# fpga_power.net
KiCad netlist of a schematic drawn in Altium Designer
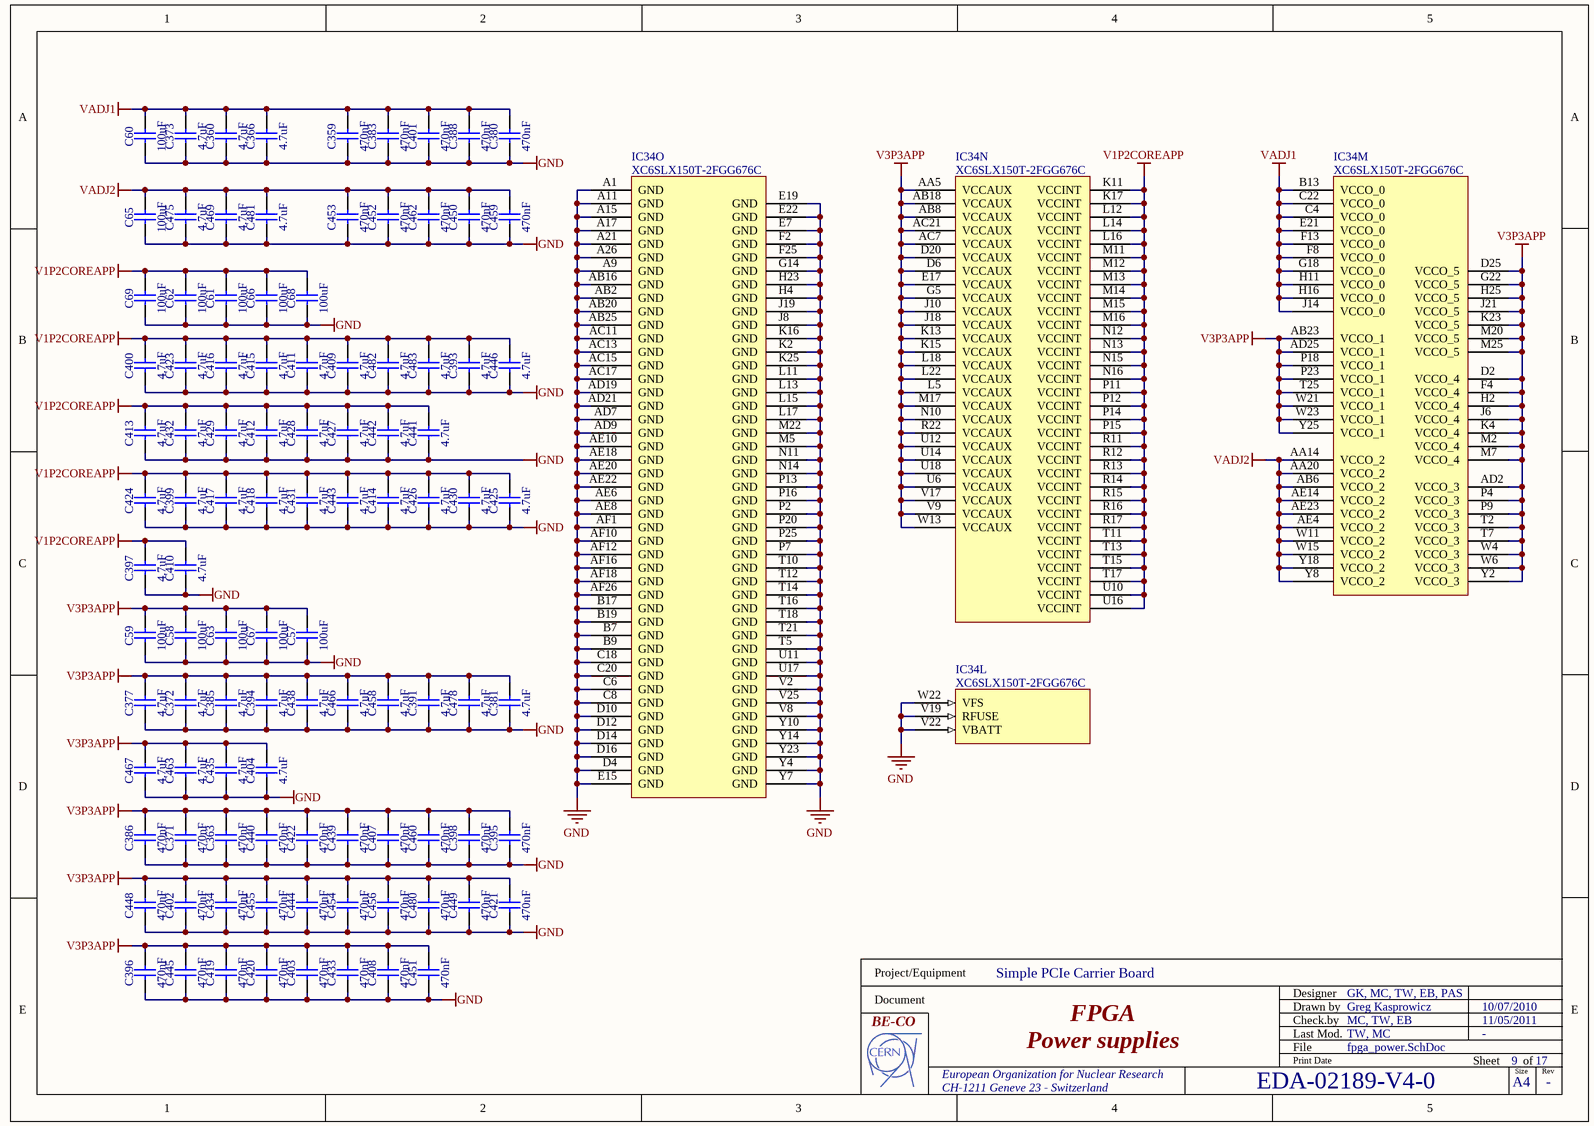
[diagram p0: fpga_power.SchDoc]

(export (version "E")
  (design (tool "Eeschema 10.0.6"))
  (components
    (comp (ref "C57")
      (value "100uF")
      (footprint "CAPC3225X270N")
      (description "Non-polarised capacitor")
      (fields
        (field (name "PART NUMBER") "CC1210_100UF_6.3V_20%_X5R")
        (field (name "VOLTAGE") "6.3V")
        (field (name "AUTHOR") "CERN DEM JLC")
      )
      (libsource (lib "Capacitors") (part "Capacitor - non polarized"))
    )
    (comp (ref "C58")
      (value "100uF")
      (footprint "CAPC3225X270N")
      (description "Non-polarised capacitor")
      (fields
        (field (name "PART NUMBER") "CC1210_100UF_6.3V_20%_X5R")
        (field (name "VOLTAGE") "6.3V")
        (field (name "AUTHOR") "CERN DEM JLC")
      )
      (libsource (lib "Capacitors") (part "Capacitor - non polarized"))
    )
    (comp (ref "C59")
      (value "100uF")
      (footprint "CAPC3225X270N")
      (description "Non-polarised capacitor")
      (fields
        (field (name "PART NUMBER") "CC1210_100UF_6.3V_20%_X5R")
        (field (name "VOLTAGE") "6.3V")
        (field (name "AUTHOR") "CERN DEM JLC")
      )
      (libsource (lib "Capacitors") (part "Capacitor - non polarized"))
    )
    (comp (ref "C60")
      (value "100uF")
      (footprint "CAPC3225X270N")
      (description "Non-polarised capacitor")
      (fields
        (field (name "PART NUMBER") "CC1210_100UF_6.3V_20%_X5R")
        (field (name "VOLTAGE") "6.3V")
        (field (name "AUTHOR") "CERN DEM JLC")
      )
      (libsource (lib "Capacitors") (part "Capacitor - non polarized"))
    )
    (comp (ref "C61")
      (value "100uF")
      (footprint "CAPC3225X270N")
      (description "Non-polarised capacitor")
      (fields
        (field (name "PART NUMBER") "CC1210_100UF_6.3V_20%_X5R")
        (field (name "VOLTAGE") "6.3V")
        (field (name "AUTHOR") "CERN DEM JLC")
      )
      (libsource (lib "Capacitors") (part "Capacitor - non polarized"))
    )
    (comp (ref "C62")
      (value "100uF")
      (footprint "CAPC3225X270N")
      (description "Non-polarised capacitor")
      (fields
        (field (name "PART NUMBER") "CC1210_100UF_6.3V_20%_X5R")
        (field (name "VOLTAGE") "6.3V")
        (field (name "AUTHOR") "CERN DEM JLC")
      )
      (libsource (lib "Capacitors") (part "Capacitor - non polarized"))
    )
    (comp (ref "C63")
      (value "100uF")
      (footprint "CAPC3225X270N")
      (description "Non-polarised capacitor")
      (fields
        (field (name "PART NUMBER") "CC1210_100UF_6.3V_20%_X5R")
        (field (name "VOLTAGE") "6.3V")
        (field (name "AUTHOR") "CERN DEM JLC")
      )
      (libsource (lib "Capacitors") (part "Capacitor - non polarized"))
    )
    (comp (ref "C65")
      (value "100uF")
      (footprint "CAPC3225X270N")
      (description "Non-polarised capacitor")
      (fields
        (field (name "PART NUMBER") "CC1210_100UF_6.3V_20%_X5R")
        (field (name "VOLTAGE") "6.3V")
        (field (name "AUTHOR") "CERN DEM JLC")
      )
      (libsource (lib "Capacitors") (part "Capacitor - non polarized"))
    )
    (comp (ref "C66")
      (value "100uF")
      (footprint "CAPC3225X270N")
      (description "Non-polarised capacitor")
      (fields
        (field (name "PART NUMBER") "CC1210_100UF_6.3V_20%_X5R")
        (field (name "VOLTAGE") "6.3V")
        (field (name "AUTHOR") "CERN DEM JLC")
      )
      (libsource (lib "Capacitors") (part "Capacitor - non polarized"))
    )
    (comp (ref "C67")
      (value "100uF")
      (footprint "CAPC3225X270N")
      (description "Non-polarised capacitor")
      (fields
        (field (name "PART NUMBER") "CC1210_100UF_6.3V_20%_X5R")
        (field (name "VOLTAGE") "6.3V")
        (field (name "AUTHOR") "CERN DEM JLC")
      )
      (libsource (lib "Capacitors") (part "Capacitor - non polarized"))
    )
    (comp (ref "C68")
      (value "100uF")
      (footprint "CAPC3225X270N")
      (description "Non-polarised capacitor")
      (fields
        (field (name "PART NUMBER") "CC1210_100UF_6.3V_20%_X5R")
        (field (name "VOLTAGE") "6.3V")
        (field (name "AUTHOR") "CERN DEM JLC")
      )
      (libsource (lib "Capacitors") (part "Capacitor - non polarized"))
    )
    (comp (ref "C69")
      (value "100uF")
      (footprint "CAPC3225X270N")
      (description "Non-polarised capacitor")
      (fields
        (field (name "PART NUMBER") "CC1210_100UF_6.3V_20%_X5R")
        (field (name "VOLTAGE") "6.3V")
        (field (name "AUTHOR") "CERN DEM JLC")
      )
      (libsource (lib "Capacitors") (part "Capacitor - non polarized"))
    )
    (comp (ref "C359")
      (value "470nF")
      (footprint "CAPC1005X55N")
      (description "Non-polarised capacitor")
      (fields
        (field (name "PART NUMBER") "CC0402_470NF_6.3V_10%_X5R")
        (field (name "VOLTAGE") "6.3V")
        (field (name "AUTHOR") "CERN DEM JLC")
      )
      (libsource (lib "Capacitors") (part "Capacitor - non polarized"))
    )
    (comp (ref "C360")
      (value "4.7uF")
      (footprint "CAPC1005X55N")
      (description "Non-polarised capacitor")
      (fields
        (field (name "PART NUMBER") "CC0402_4.7UF_4V_20%_X5R")
        (field (name "VOLTAGE") "4V")
        (field (name "AUTHOR") "CERN DEM JLC")
      )
      (libsource (lib "Capacitors") (part "Capacitor - non polarized"))
    )
    (comp (ref "C363")
      (value "470nF")
      (footprint "CAPC1005X55N")
      (description "Non-polarised capacitor")
      (fields
        (field (name "PART NUMBER") "CC0402_470NF_6.3V_10%_X5R")
        (field (name "VOLTAGE") "6.3V")
        (field (name "AUTHOR") "CERN DEM JLC")
      )
      (libsource (lib "Capacitors") (part "Capacitor - non polarized"))
    )
    (comp (ref "C366")
      (value "4.7uF")
      (footprint "CAPC1005X55N")
      (description "Non-polarised capacitor")
      (fields
        (field (name "PART NUMBER") "CC0402_4.7UF_4V_20%_X5R")
        (field (name "VOLTAGE") "4V")
        (field (name "AUTHOR") "CERN DEM JLC")
      )
      (libsource (lib "Capacitors") (part "Capacitor - non polarized"))
    )
    (comp (ref "C371")
      (value "470nF")
      (footprint "CAPC1005X55N")
      (description "Non-polarised capacitor")
      (fields
        (field (name "PART NUMBER") "CC0402_470NF_6.3V_10%_X5R")
        (field (name "VOLTAGE") "6.3V")
        (field (name "AUTHOR") "CERN DEM JLC")
      )
      (libsource (lib "Capacitors") (part "Capacitor - non polarized"))
    )
    (comp (ref "C372")
      (value "4.7uF")
      (footprint "CAPC1005X55N")
      (description "Non-polarised capacitor")
      (fields
        (field (name "PART NUMBER") "CC0402_4.7UF_4V_20%_X5R")
        (field (name "VOLTAGE") "4V")
        (field (name "AUTHOR") "CERN DEM JLC")
      )
      (libsource (lib "Capacitors") (part "Capacitor - non polarized"))
    )
    (comp (ref "C373")
      (value "4.7uF")
      (footprint "CAPC1005X55N")
      (description "Non-polarised capacitor")
      (fields
        (field (name "PART NUMBER") "CC0402_4.7UF_4V_20%_X5R")
        (field (name "VOLTAGE") "4V")
        (field (name "AUTHOR") "CERN DEM JLC")
      )
      (libsource (lib "Capacitors") (part "Capacitor - non polarized"))
    )
    (comp (ref "C377")
      (value "4.7uF")
      (footprint "CAPC1005X55N")
      (description "Non-polarised capacitor")
      (fields
        (field (name "PART NUMBER") "CC0402_4.7UF_4V_20%_X5R")
        (field (name "VOLTAGE") "4V")
        (field (name "AUTHOR") "CERN DEM JLC")
      )
      (libsource (lib "Capacitors") (part "Capacitor - non polarized"))
    )
    (comp (ref "C380")
      (value "470nF")
      (footprint "CAPC1005X55N")
      (description "Non-polarised capacitor")
      (fields
        (field (name "PART NUMBER") "CC0402_470NF_6.3V_10%_X5R")
        (field (name "VOLTAGE") "6.3V")
        (field (name "AUTHOR") "CERN DEM JLC")
      )
      (libsource (lib "Capacitors") (part "Capacitor - non polarized"))
    )
    (comp (ref "C381")
      (value "4.7uF")
      (footprint "CAPC1005X55N")
      (description "Non-polarised capacitor")
      (fields
        (field (name "PART NUMBER") "CC0402_4.7UF_4V_20%_X5R")
        (field (name "VOLTAGE") "4V")
        (field (name "AUTHOR") "CERN DEM JLC")
      )
      (libsource (lib "Capacitors") (part "Capacitor - non polarized"))
    )
    (comp (ref "C383")
      (value "470nF")
      (footprint "CAPC1005X55N")
      (description "Non-polarised capacitor")
      (fields
        (field (name "PART NUMBER") "CC0402_470NF_6.3V_10%_X5R")
        (field (name "VOLTAGE") "6.3V")
        (field (name "AUTHOR") "CERN DEM JLC")
      )
      (libsource (lib "Capacitors") (part "Capacitor - non polarized"))
    )
    (comp (ref "C385")
      (value "4.7uF")
      (footprint "CAPC1005X55N")
      (description "Non-polarised capacitor")
      (fields
        (field (name "PART NUMBER") "CC0402_4.7UF_4V_20%_X5R")
        (field (name "VOLTAGE") "4V")
        (field (name "AUTHOR") "CERN DEM JLC")
      )
      (libsource (lib "Capacitors") (part "Capacitor - non polarized"))
    )
    (comp (ref "C386")
      (value "470nF")
      (footprint "CAPC1005X55N")
      (description "Non-polarised capacitor")
      (fields
        (field (name "PART NUMBER") "CC0402_470NF_6.3V_10%_X5R")
        (field (name "VOLTAGE") "6.3V")
        (field (name "AUTHOR") "CERN DEM JLC")
      )
      (libsource (lib "Capacitors") (part "Capacitor - non polarized"))
    )
    (comp (ref "C388")
      (value "470nF")
      (footprint "CAPC1005X55N")
      (description "Non-polarised capacitor")
      (fields
        (field (name "PART NUMBER") "CC0402_470NF_6.3V_10%_X5R")
        (field (name "VOLTAGE") "6.3V")
        (field (name "AUTHOR") "CERN DEM JLC")
      )
      (libsource (lib "Capacitors") (part "Capacitor - non polarized"))
    )
    (comp (ref "C391")
      (value "4.7uF")
      (footprint "CAPC1005X55N")
      (description "Non-polarised capacitor")
      (fields
        (field (name "PART NUMBER") "CC0402_4.7UF_4V_20%_X5R")
        (field (name "VOLTAGE") "4V")
        (field (name "AUTHOR") "CERN DEM JLC")
      )
      (libsource (lib "Capacitors") (part "Capacitor - non polarized"))
    )
    (comp (ref "C393")
      (value "4.7uF")
      (footprint "CAPC1005X55N")
      (description "Non-polarised capacitor")
      (fields
        (field (name "PART NUMBER") "CC0402_4.7UF_4V_20%_X5R")
        (field (name "VOLTAGE") "4V")
        (field (name "AUTHOR") "CERN DEM JLC")
      )
      (libsource (lib "Capacitors") (part "Capacitor - non polarized"))
    )
    (comp (ref "C394")
      (value "4.7uF")
      (footprint "CAPC1005X55N")
      (description "Non-polarised capacitor")
      (fields
        (field (name "PART NUMBER") "CC0402_4.7UF_4V_20%_X5R")
        (field (name "VOLTAGE") "4V")
        (field (name "AUTHOR") "CERN DEM JLC")
      )
      (libsource (lib "Capacitors") (part "Capacitor - non polarized"))
    )
    (comp (ref "C395")
      (value "470nF")
      (footprint "CAPC1005X55N")
      (description "Non-polarised capacitor")
      (fields
        (field (name "PART NUMBER") "CC0402_470NF_6.3V_10%_X5R")
        (field (name "VOLTAGE") "6.3V")
        (field (name "AUTHOR") "CERN DEM JLC")
      )
      (libsource (lib "Capacitors") (part "Capacitor - non polarized"))
    )
    (comp (ref "C396")
      (value "470nF")
      (footprint "CAPC1005X55N")
      (description "Non-polarised capacitor")
      (fields
        (field (name "PART NUMBER") "CC0402_470NF_6.3V_10%_X5R")
        (field (name "VOLTAGE") "6.3V")
        (field (name "AUTHOR") "CERN DEM JLC")
      )
      (libsource (lib "Capacitors") (part "Capacitor - non polarized"))
    )
    (comp (ref "C397")
      (value "4.7uF")
      (footprint "CAPC1005X55N")
      (description "Non-polarised capacitor")
      (fields
        (field (name "PART NUMBER") "CC0402_4.7UF_4V_20%_X5R")
        (field (name "VOLTAGE") "4V")
        (field (name "AUTHOR") "CERN DEM JLC")
      )
      (libsource (lib "Capacitors") (part "Capacitor - non polarized"))
    )
    (comp (ref "C398")
      (value "470nF")
      (footprint "CAPC1005X55N")
      (description "Non-polarised capacitor")
      (fields
        (field (name "PART NUMBER") "CC0402_470NF_6.3V_10%_X5R")
        (field (name "VOLTAGE") "6.3V")
        (field (name "AUTHOR") "CERN DEM JLC")
      )
      (libsource (lib "Capacitors") (part "Capacitor - non polarized"))
    )
    (comp (ref "C399")
      (value "4.7uF")
      (footprint "CAPC1005X55N")
      (description "Non-polarised capacitor")
      (fields
        (field (name "PART NUMBER") "CC0402_4.7UF_4V_20%_X5R")
        (field (name "VOLTAGE") "4V")
        (field (name "AUTHOR") "CERN DEM JLC")
      )
      (libsource (lib "Capacitors") (part "Capacitor - non polarized"))
    )
    (comp (ref "C400")
      (value "4.7uF")
      (footprint "CAPC1005X55N")
      (description "Non-polarised capacitor")
      (fields
        (field (name "PART NUMBER") "CC0402_4.7UF_4V_20%_X5R")
        (field (name "VOLTAGE") "4V")
        (field (name "AUTHOR") "CERN DEM JLC")
      )
      (libsource (lib "Capacitors") (part "Capacitor - non polarized"))
    )
    (comp (ref "C401")
      (value "470nF")
      (footprint "CAPC1005X55N")
      (description "Non-polarised capacitor")
      (fields
        (field (name "PART NUMBER") "CC0402_470NF_6.3V_10%_X5R")
        (field (name "VOLTAGE") "6.3V")
        (field (name "AUTHOR") "CERN DEM JLC")
      )
      (libsource (lib "Capacitors") (part "Capacitor - non polarized"))
    )
    (comp (ref "C402")
      (value "470nF")
      (footprint "CAPC1005X55N")
      (description "Non-polarised capacitor")
      (fields
        (field (name "PART NUMBER") "CC0402_470NF_6.3V_10%_X5R")
        (field (name "VOLTAGE") "6.3V")
        (field (name "AUTHOR") "CERN DEM JLC")
      )
      (libsource (lib "Capacitors") (part "Capacitor - non polarized"))
    )
    (comp (ref "C403")
      (value "470nF")
      (footprint "CAPC1005X55N")
      (description "Non-polarised capacitor")
      (fields
        (field (name "PART NUMBER") "CC0402_470NF_6.3V_10%_X5R")
        (field (name "VOLTAGE") "6.3V")
        (field (name "AUTHOR") "CERN DEM JLC")
      )
      (libsource (lib "Capacitors") (part "Capacitor - non polarized"))
    )
    (comp (ref "C404")
      (value "4.7uF")
      (footprint "CAPC1005X55N")
      (description "Non-polarised capacitor")
      (fields
        (field (name "PART NUMBER") "CC0402_4.7UF_4V_20%_X5R")
        (field (name "VOLTAGE") "4V")
        (field (name "AUTHOR") "CERN DEM JLC")
      )
      (libsource (lib "Capacitors") (part "Capacitor - non polarized"))
    )
    (comp (ref "C407")
      (value "470nF")
      (footprint "CAPC1005X55N")
      (description "Non-polarised capacitor")
      (fields
        (field (name "PART NUMBER") "CC0402_470NF_6.3V_10%_X5R")
        (field (name "VOLTAGE") "6.3V")
        (field (name "AUTHOR") "CERN DEM JLC")
      )
      (libsource (lib "Capacitors") (part "Capacitor - non polarized"))
    )
    (comp (ref "C408")
      (value "470nF")
      (footprint "CAPC1005X55N")
      (description "Non-polarised capacitor")
      (fields
        (field (name "PART NUMBER") "CC0402_470NF_6.3V_10%_X5R")
        (field (name "VOLTAGE") "6.3V")
        (field (name "AUTHOR") "CERN DEM JLC")
      )
      (libsource (lib "Capacitors") (part "Capacitor - non polarized"))
    )
    (comp (ref "C409")
      (value "4.7uF")
      (footprint "CAPC1005X55N")
      (description "Non-polarised capacitor")
      (fields
        (field (name "PART NUMBER") "CC0402_4.7UF_4V_20%_X5R")
        (field (name "VOLTAGE") "4V")
        (field (name "AUTHOR") "CERN DEM JLC")
      )
      (libsource (lib "Capacitors") (part "Capacitor - non polarized"))
    )
    (comp (ref "C410")
      (value "4.7uF")
      (footprint "CAPC1005X55N")
      (description "Non-polarised capacitor")
      (fields
        (field (name "PART NUMBER") "CC0402_4.7UF_4V_20%_X5R")
        (field (name "VOLTAGE") "4V")
        (field (name "AUTHOR") "CERN DEM JLC")
      )
      (libsource (lib "Capacitors") (part "Capacitor - non polarized"))
    )
    (comp (ref "C411")
      (value "4.7uF")
      (footprint "CAPC1005X55N")
      (description "Non-polarised capacitor")
      (fields
        (field (name "PART NUMBER") "CC0402_4.7UF_4V_20%_X5R")
        (field (name "VOLTAGE") "4V")
        (field (name "AUTHOR") "CERN DEM JLC")
      )
      (libsource (lib "Capacitors") (part "Capacitor - non polarized"))
    )
    (comp (ref "C412")
      (value "4.7uF")
      (footprint "CAPC1005X55N")
      (description "Non-polarised capacitor")
      (fields
        (field (name "PART NUMBER") "CC0402_4.7UF_4V_20%_X5R")
        (field (name "VOLTAGE") "4V")
        (field (name "AUTHOR") "CERN DEM JLC")
      )
      (libsource (lib "Capacitors") (part "Capacitor - non polarized"))
    )
    (comp (ref "C413")
      (value "4.7uF")
      (footprint "CAPC1005X55N")
      (description "Non-polarised capacitor")
      (fields
        (field (name "PART NUMBER") "CC0402_4.7UF_4V_20%_X5R")
        (field (name "VOLTAGE") "4V")
        (field (name "AUTHOR") "CERN DEM JLC")
      )
      (libsource (lib "Capacitors") (part "Capacitor - non polarized"))
    )
    (comp (ref "C414")
      (value "4.7uF")
      (footprint "CAPC1005X55N")
      (description "Non-polarised capacitor")
      (fields
        (field (name "PART NUMBER") "CC0402_4.7UF_4V_20%_X5R")
        (field (name "VOLTAGE") "4V")
        (field (name "AUTHOR") "CERN DEM JLC")
      )
      (libsource (lib "Capacitors") (part "Capacitor - non polarized"))
    )
    (comp (ref "C415")
      (value "4.7uF")
      (footprint "CAPC1005X55N")
      (description "Non-polarised capacitor")
      (fields
        (field (name "PART NUMBER") "CC0402_4.7UF_4V_20%_X5R")
        (field (name "VOLTAGE") "4V")
        (field (name "AUTHOR") "CERN DEM JLC")
      )
      (libsource (lib "Capacitors") (part "Capacitor - non polarized"))
    )
    (comp (ref "C416")
      (value "4.7uF")
      (footprint "CAPC1005X55N")
      (description "Non-polarised capacitor")
      (fields
        (field (name "PART NUMBER") "CC0402_4.7UF_4V_20%_X5R")
        (field (name "VOLTAGE") "4V")
        (field (name "AUTHOR") "CERN DEM JLC")
      )
      (libsource (lib "Capacitors") (part "Capacitor - non polarized"))
    )
    (comp (ref "C417")
      (value "4.7uF")
      (footprint "CAPC1005X55N")
      (description "Non-polarised capacitor")
      (fields
        (field (name "PART NUMBER") "CC0402_4.7UF_4V_20%_X5R")
        (field (name "VOLTAGE") "4V")
        (field (name "AUTHOR") "CERN DEM JLC")
      )
      (libsource (lib "Capacitors") (part "Capacitor - non polarized"))
    )
    (comp (ref "C418")
      (value "4.7uF")
      (footprint "CAPC1005X55N")
      (description "Non-polarised capacitor")
      (fields
        (field (name "PART NUMBER") "CC0402_4.7UF_4V_20%_X5R")
        (field (name "VOLTAGE") "4V")
        (field (name "AUTHOR") "CERN DEM JLC")
      )
      (libsource (lib "Capacitors") (part "Capacitor - non polarized"))
    )
    (comp (ref "C419")
      (value "470nF")
      (footprint "CAPC1005X55N")
      (description "Non-polarised capacitor")
      (fields
        (field (name "PART NUMBER") "CC0402_470NF_6.3V_10%_X5R")
        (field (name "VOLTAGE") "6.3V")
        (field (name "AUTHOR") "CERN DEM JLC")
      )
      (libsource (lib "Capacitors") (part "Capacitor - non polarized"))
    )
    (comp (ref "C420")
      (value "470nF")
      (footprint "CAPC1005X55N")
      (description "Non-polarised capacitor")
      (fields
        (field (name "PART NUMBER") "CC0402_470NF_6.3V_10%_X5R")
        (field (name "VOLTAGE") "6.3V")
        (field (name "AUTHOR") "CERN DEM JLC")
      )
      (libsource (lib "Capacitors") (part "Capacitor - non polarized"))
    )
    (comp (ref "C421")
      (value "470nF")
      (footprint "CAPC1005X55N")
      (description "Non-polarised capacitor")
      (fields
        (field (name "PART NUMBER") "CC0402_470NF_6.3V_10%_X5R")
        (field (name "VOLTAGE") "6.3V")
        (field (name "AUTHOR") "CERN DEM JLC")
      )
      (libsource (lib "Capacitors") (part "Capacitor - non polarized"))
    )
    (comp (ref "C422")
      (value "470nF")
      (footprint "CAPC1005X55N")
      (description "Non-polarised capacitor")
      (fields
        (field (name "PART NUMBER") "CC0402_470NF_6.3V_10%_X5R")
        (field (name "VOLTAGE") "6.3V")
        (field (name "AUTHOR") "CERN DEM JLC")
      )
      (libsource (lib "Capacitors") (part "Capacitor - non polarized"))
    )
    (comp (ref "C423")
      (value "4.7uF")
      (footprint "CAPC1005X55N")
      (description "Non-polarised capacitor")
      (fields
        (field (name "PART NUMBER") "CC0402_4.7UF_4V_20%_X5R")
        (field (name "VOLTAGE") "4V")
        (field (name "AUTHOR") "CERN DEM JLC")
      )
      (libsource (lib "Capacitors") (part "Capacitor - non polarized"))
    )
    (comp (ref "C424")
      (value "4.7uF")
      (footprint "CAPC1005X55N")
      (description "Non-polarised capacitor")
      (fields
        (field (name "PART NUMBER") "CC0402_4.7UF_4V_20%_X5R")
        (field (name "VOLTAGE") "4V")
        (field (name "AUTHOR") "CERN DEM JLC")
      )
      (libsource (lib "Capacitors") (part "Capacitor - non polarized"))
    )
    (comp (ref "C425")
      (value "4.7uF")
      (footprint "CAPC1005X55N")
      (description "Non-polarised capacitor")
      (fields
        (field (name "PART NUMBER") "CC0402_4.7UF_4V_20%_X5R")
        (field (name "VOLTAGE") "4V")
        (field (name "AUTHOR") "CERN DEM JLC")
      )
      (libsource (lib "Capacitors") (part "Capacitor - non polarized"))
    )
    (comp (ref "C426")
      (value "4.7uF")
      (footprint "CAPC1005X55N")
      (description "Non-polarised capacitor")
      (fields
        (field (name "PART NUMBER") "CC0402_4.7UF_4V_20%_X5R")
        (field (name "VOLTAGE") "4V")
        (field (name "AUTHOR") "CERN DEM JLC")
      )
      (libsource (lib "Capacitors") (part "Capacitor - non polarized"))
    )
    (comp (ref "C427")
      (value "4.7uF")
      (footprint "CAPC1005X55N")
      (description "Non-polarised capacitor")
      (fields
        (field (name "PART NUMBER") "CC0402_4.7UF_4V_20%_X5R")
        (field (name "VOLTAGE") "4V")
        (field (name "AUTHOR") "CERN DEM JLC")
      )
      (libsource (lib "Capacitors") (part "Capacitor - non polarized"))
    )
    (comp (ref "C428")
      (value "4.7uF")
      (footprint "CAPC1005X55N")
      (description "Non-polarised capacitor")
      (fields
        (field (name "PART NUMBER") "CC0402_4.7UF_4V_20%_X5R")
        (field (name "VOLTAGE") "4V")
        (field (name "AUTHOR") "CERN DEM JLC")
      )
      (libsource (lib "Capacitors") (part "Capacitor - non polarized"))
    )
    (comp (ref "C429")
      (value "4.7uF")
      (footprint "CAPC1005X55N")
      (description "Non-polarised capacitor")
      (fields
        (field (name "PART NUMBER") "CC0402_4.7UF_4V_20%_X5R")
        (field (name "VOLTAGE") "4V")
        (field (name "AUTHOR") "CERN DEM JLC")
      )
      (libsource (lib "Capacitors") (part "Capacitor - non polarized"))
    )
    (comp (ref "C430")
      (value "4.7uF")
      (footprint "CAPC1005X55N")
      (description "Non-polarised capacitor")
      (fields
        (field (name "PART NUMBER") "CC0402_4.7UF_4V_20%_X5R")
        (field (name "VOLTAGE") "4V")
        (field (name "AUTHOR") "CERN DEM JLC")
      )
      (libsource (lib "Capacitors") (part "Capacitor - non polarized"))
    )
    (comp (ref "C431")
      (value "4.7uF")
      (footprint "CAPC1005X55N")
      (description "Non-polarised capacitor")
      (fields
        (field (name "PART NUMBER") "CC0402_4.7UF_4V_20%_X5R")
        (field (name "VOLTAGE") "4V")
        (field (name "AUTHOR") "CERN DEM JLC")
      )
      (libsource (lib "Capacitors") (part "Capacitor - non polarized"))
    )
    (comp (ref "C432")
      (value "4.7uF")
      (footprint "CAPC1005X55N")
      (description "Non-polarised capacitor")
      (fields
        (field (name "PART NUMBER") "CC0402_4.7UF_4V_20%_X5R")
        (field (name "VOLTAGE") "4V")
        (field (name "AUTHOR") "CERN DEM JLC")
      )
      (libsource (lib "Capacitors") (part "Capacitor - non polarized"))
    )
    (comp (ref "C433")
      (value "470nF")
      (footprint "CAPC1005X55N")
      (description "Non-polarised capacitor")
      (fields
        (field (name "PART NUMBER") "CC0402_470NF_6.3V_10%_X5R")
        (field (name "VOLTAGE") "6.3V")
        (field (name "AUTHOR") "CERN DEM JLC")
      )
      (libsource (lib "Capacitors") (part "Capacitor - non polarized"))
    )
    (comp (ref "C434")
      (value "470nF")
      (footprint "CAPC1005X55N")
      (description "Non-polarised capacitor")
      (fields
        (field (name "PART NUMBER") "CC0402_470NF_6.3V_10%_X5R")
        (field (name "VOLTAGE") "6.3V")
        (field (name "AUTHOR") "CERN DEM JLC")
      )
      (libsource (lib "Capacitors") (part "Capacitor - non polarized"))
    )
    (comp (ref "C435")
      (value "4.7uF")
      (footprint "CAPC1005X55N")
      (description "Non-polarised capacitor")
      (fields
        (field (name "PART NUMBER") "CC0402_4.7UF_4V_20%_X5R")
        (field (name "VOLTAGE") "4V")
        (field (name "AUTHOR") "CERN DEM JLC")
      )
      (libsource (lib "Capacitors") (part "Capacitor - non polarized"))
    )
    (comp (ref "C438")
      (value "4.7uF")
      (footprint "CAPC1005X55N")
      (description "Non-polarised capacitor")
      (fields
        (field (name "PART NUMBER") "CC0402_4.7UF_4V_20%_X5R")
        (field (name "VOLTAGE") "4V")
        (field (name "AUTHOR") "CERN DEM JLC")
      )
      (libsource (lib "Capacitors") (part "Capacitor - non polarized"))
    )
    (comp (ref "C439")
      (value "470nF")
      (footprint "CAPC1005X55N")
      (description "Non-polarised capacitor")
      (fields
        (field (name "PART NUMBER") "CC0402_470NF_6.3V_10%_X5R")
        (field (name "VOLTAGE") "6.3V")
        (field (name "AUTHOR") "CERN DEM JLC")
      )
      (libsource (lib "Capacitors") (part "Capacitor - non polarized"))
    )
    (comp (ref "C440")
      (value "470nF")
      (footprint "CAPC1005X55N")
      (description "Non-polarised capacitor")
      (fields
        (field (name "PART NUMBER") "CC0402_470NF_6.3V_10%_X5R")
        (field (name "VOLTAGE") "6.3V")
        (field (name "AUTHOR") "CERN DEM JLC")
      )
      (libsource (lib "Capacitors") (part "Capacitor - non polarized"))
    )
    (comp (ref "C441")
      (value "4.7uF")
      (footprint "CAPC1005X55N")
      (description "Non-polarised capacitor")
      (fields
        (field (name "PART NUMBER") "CC0402_4.7UF_4V_20%_X5R")
        (field (name "VOLTAGE") "4V")
        (field (name "AUTHOR") "CERN DEM JLC")
      )
      (libsource (lib "Capacitors") (part "Capacitor - non polarized"))
    )
    (comp (ref "C442")
      (value "4.7uF")
      (footprint "CAPC1005X55N")
      (description "Non-polarised capacitor")
      (fields
        (field (name "PART NUMBER") "CC0402_4.7UF_4V_20%_X5R")
        (field (name "VOLTAGE") "4V")
        (field (name "AUTHOR") "CERN DEM JLC")
      )
      (libsource (lib "Capacitors") (part "Capacitor - non polarized"))
    )
    (comp (ref "C443")
      (value "4.7uF")
      (footprint "CAPC1005X55N")
      (description "Non-polarised capacitor")
      (fields
        (field (name "PART NUMBER") "CC0402_4.7UF_4V_20%_X5R")
        (field (name "VOLTAGE") "4V")
        (field (name "AUTHOR") "CERN DEM JLC")
      )
      (libsource (lib "Capacitors") (part "Capacitor - non polarized"))
    )
    (comp (ref "C444")
      (value "470nF")
      (footprint "CAPC1005X55N")
      (description "Non-polarised capacitor")
      (fields
        (field (name "PART NUMBER") "CC0402_470NF_6.3V_10%_X5R")
        (field (name "VOLTAGE") "6.3V")
        (field (name "AUTHOR") "CERN DEM JLC")
      )
      (libsource (lib "Capacitors") (part "Capacitor - non polarized"))
    )
    (comp (ref "C445")
      (value "470nF")
      (footprint "CAPC1005X55N")
      (description "Non-polarised capacitor")
      (fields
        (field (name "PART NUMBER") "CC0402_470NF_6.3V_10%_X5R")
        (field (name "VOLTAGE") "6.3V")
        (field (name "AUTHOR") "CERN DEM JLC")
      )
      (libsource (lib "Capacitors") (part "Capacitor - non polarized"))
    )
    (comp (ref "C446")
      (value "4.7uF")
      (footprint "CAPC1005X55N")
      (description "Non-polarised capacitor")
      (fields
        (field (name "PART NUMBER") "CC0402_4.7UF_4V_20%_X5R")
        (field (name "VOLTAGE") "4V")
        (field (name "AUTHOR") "CERN DEM JLC")
      )
      (libsource (lib "Capacitors") (part "Capacitor - non polarized"))
    )
    (comp (ref "C448")
      (value "470nF")
      (footprint "CAPC1005X55N")
      (description "Non-polarised capacitor")
      (fields
        (field (name "PART NUMBER") "CC0402_470NF_6.3V_10%_X5R")
        (field (name "VOLTAGE") "6.3V")
        (field (name "AUTHOR") "CERN DEM JLC")
      )
      (libsource (lib "Capacitors") (part "Capacitor - non polarized"))
    )
    (comp (ref "C449")
      (value "470nF")
      (footprint "CAPC1005X55N")
      (description "Non-polarised capacitor")
      (fields
        (field (name "PART NUMBER") "CC0402_470NF_6.3V_10%_X5R")
        (field (name "VOLTAGE") "6.3V")
        (field (name "AUTHOR") "CERN DEM JLC")
      )
      (libsource (lib "Capacitors") (part "Capacitor - non polarized"))
    )
    (comp (ref "C450")
      (value "470nF")
      (footprint "CAPC1005X55N")
      (description "Non-polarised capacitor")
      (fields
        (field (name "PART NUMBER") "CC0402_470NF_6.3V_10%_X5R")
        (field (name "VOLTAGE") "6.3V")
        (field (name "AUTHOR") "CERN DEM JLC")
      )
      (libsource (lib "Capacitors") (part "Capacitor - non polarized"))
    )
    (comp (ref "C451")
      (value "470nF")
      (footprint "CAPC1005X55N")
      (description "Non-polarised capacitor")
      (fields
        (field (name "PART NUMBER") "CC0402_470NF_6.3V_10%_X5R")
        (field (name "VOLTAGE") "6.3V")
        (field (name "AUTHOR") "CERN DEM JLC")
      )
      (libsource (lib "Capacitors") (part "Capacitor - non polarized"))
    )
    (comp (ref "C452")
      (value "470nF")
      (footprint "CAPC1005X55N")
      (description "Non-polarised capacitor")
      (fields
        (field (name "PART NUMBER") "CC0402_470NF_6.3V_10%_X5R")
        (field (name "VOLTAGE") "6.3V")
        (field (name "AUTHOR") "CERN DEM JLC")
      )
      (libsource (lib "Capacitors") (part "Capacitor - non polarized"))
    )
    (comp (ref "C453")
      (value "470nF")
      (footprint "CAPC1005X55N")
      (description "Non-polarised capacitor")
      (fields
        (field (name "PART NUMBER") "CC0402_470NF_6.3V_10%_X5R")
        (field (name "VOLTAGE") "6.3V")
        (field (name "AUTHOR") "CERN DEM JLC")
      )
      (libsource (lib "Capacitors") (part "Capacitor - non polarized"))
    )
    (comp (ref "C454")
      (value "470nF")
      (footprint "CAPC1005X55N")
      (description "Non-polarised capacitor")
      (fields
        (field (name "PART NUMBER") "CC0402_470NF_6.3V_10%_X5R")
        (field (name "VOLTAGE") "6.3V")
        (field (name "AUTHOR") "CERN DEM JLC")
      )
      (libsource (lib "Capacitors") (part "Capacitor - non polarized"))
    )
    (comp (ref "C455")
      (value "470nF")
      (footprint "CAPC1005X55N")
      (description "Non-polarised capacitor")
      (fields
        (field (name "PART NUMBER") "CC0402_470NF_6.3V_10%_X5R")
        (field (name "VOLTAGE") "6.3V")
        (field (name "AUTHOR") "CERN DEM JLC")
      )
      (libsource (lib "Capacitors") (part "Capacitor - non polarized"))
    )
    (comp (ref "C456")
      (value "470nF")
      (footprint "CAPC1005X55N")
      (description "Non-polarised capacitor")
      (fields
        (field (name "PART NUMBER") "CC0402_470NF_6.3V_10%_X5R")
        (field (name "VOLTAGE") "6.3V")
        (field (name "AUTHOR") "CERN DEM JLC")
      )
      (libsource (lib "Capacitors") (part "Capacitor - non polarized"))
    )
    (comp (ref "C458")
      (value "4.7uF")
      (footprint "CAPC1005X55N")
      (description "Non-polarised capacitor")
      (fields
        (field (name "PART NUMBER") "CC0402_4.7UF_4V_20%_X5R")
        (field (name "VOLTAGE") "4V")
        (field (name "AUTHOR") "CERN DEM JLC")
      )
      (libsource (lib "Capacitors") (part "Capacitor - non polarized"))
    )
    (comp (ref "C459")
      (value "470nF")
      (footprint "CAPC1005X55N")
      (description "Non-polarised capacitor")
      (fields
        (field (name "PART NUMBER") "CC0402_470NF_6.3V_10%_X5R")
        (field (name "VOLTAGE") "6.3V")
        (field (name "AUTHOR") "CERN DEM JLC")
      )
      (libsource (lib "Capacitors") (part "Capacitor - non polarized"))
    )
    (comp (ref "C460")
      (value "470nF")
      (footprint "CAPC1005X55N")
      (description "Non-polarised capacitor")
      (fields
        (field (name "PART NUMBER") "CC0402_470NF_6.3V_10%_X5R")
        (field (name "VOLTAGE") "6.3V")
        (field (name "AUTHOR") "CERN DEM JLC")
      )
      (libsource (lib "Capacitors") (part "Capacitor - non polarized"))
    )
    (comp (ref "C462")
      (value "470nF")
      (footprint "CAPC1005X55N")
      (description "Non-polarised capacitor")
      (fields
        (field (name "PART NUMBER") "CC0402_470NF_6.3V_10%_X5R")
        (field (name "VOLTAGE") "6.3V")
        (field (name "AUTHOR") "CERN DEM JLC")
      )
      (libsource (lib "Capacitors") (part "Capacitor - non polarized"))
    )
    (comp (ref "C463")
      (value "4.7uF")
      (footprint "CAPC1005X55N")
      (description "Non-polarised capacitor")
      (fields
        (field (name "PART NUMBER") "CC0402_4.7UF_4V_20%_X5R")
        (field (name "VOLTAGE") "4V")
        (field (name "AUTHOR") "CERN DEM JLC")
      )
      (libsource (lib "Capacitors") (part "Capacitor - non polarized"))
    )
    (comp (ref "C466")
      (value "4.7uF")
      (footprint "CAPC1005X55N")
      (description "Non-polarised capacitor")
      (fields
        (field (name "PART NUMBER") "CC0402_4.7UF_4V_20%_X5R")
        (field (name "VOLTAGE") "4V")
        (field (name "AUTHOR") "CERN DEM JLC")
      )
      (libsource (lib "Capacitors") (part "Capacitor - non polarized"))
    )
    (comp (ref "C467")
      (value "4.7uF")
      (footprint "CAPC1005X55N")
      (description "Non-polarised capacitor")
      (fields
        (field (name "PART NUMBER") "CC0402_4.7UF_4V_20%_X5R")
        (field (name "VOLTAGE") "4V")
        (field (name "AUTHOR") "CERN DEM JLC")
      )
      (libsource (lib "Capacitors") (part "Capacitor - non polarized"))
    )
    (comp (ref "C469")
      (value "4.7uF")
      (footprint "CAPC1005X55N")
      (description "Non-polarised capacitor")
      (fields
        (field (name "PART NUMBER") "CC0402_4.7UF_4V_20%_X5R")
        (field (name "VOLTAGE") "4V")
        (field (name "AUTHOR") "CERN DEM JLC")
      )
      (libsource (lib "Capacitors") (part "Capacitor - non polarized"))
    )
    (comp (ref "C475")
      (value "4.7uF")
      (footprint "CAPC1005X55N")
      (description "Non-polarised capacitor")
      (fields
        (field (name "PART NUMBER") "CC0402_4.7UF_4V_20%_X5R")
        (field (name "VOLTAGE") "4V")
        (field (name "AUTHOR") "CERN DEM JLC")
      )
      (libsource (lib "Capacitors") (part "Capacitor - non polarized"))
    )
    (comp (ref "C478")
      (value "4.7uF")
      (footprint "CAPC1005X55N")
      (description "Non-polarised capacitor")
      (fields
        (field (name "PART NUMBER") "CC0402_4.7UF_4V_20%_X5R")
        (field (name "VOLTAGE") "4V")
        (field (name "AUTHOR") "CERN DEM JLC")
      )
      (libsource (lib "Capacitors") (part "Capacitor - non polarized"))
    )
    (comp (ref "C480")
      (value "470nF")
      (footprint "CAPC1005X55N")
      (description "Non-polarised capacitor")
      (fields
        (field (name "PART NUMBER") "CC0402_470NF_6.3V_10%_X5R")
        (field (name "VOLTAGE") "6.3V")
        (field (name "AUTHOR") "CERN DEM JLC")
      )
      (libsource (lib "Capacitors") (part "Capacitor - non polarized"))
    )
    (comp (ref "C481")
      (value "4.7uF")
      (footprint "CAPC1005X55N")
      (description "Non-polarised capacitor")
      (fields
        (field (name "PART NUMBER") "CC0402_4.7UF_4V_20%_X5R")
        (field (name "VOLTAGE") "4V")
        (field (name "AUTHOR") "CERN DEM JLC")
      )
      (libsource (lib "Capacitors") (part "Capacitor - non polarized"))
    )
    (comp (ref "C482")
      (value "4.7uF")
      (footprint "CAPC1005X55N")
      (description "Non-polarised capacitor")
      (fields
        (field (name "PART NUMBER") "CC0402_4.7UF_4V_20%_X5R")
        (field (name "VOLTAGE") "4V")
        (field (name "AUTHOR") "CERN DEM JLC")
      )
      (libsource (lib "Capacitors") (part "Capacitor - non polarized"))
    )
    (comp (ref "C483")
      (value "4.7uF")
      (footprint "CAPC1005X55N")
      (description "Non-polarised capacitor")
      (fields
        (field (name "PART NUMBER") "CC0402_4.7UF_4V_20%_X5R")
        (field (name "VOLTAGE") "4V")
        (field (name "AUTHOR") "CERN DEM JLC")
      )
      (libsource (lib "Capacitors") (part "Capacitor - non polarized"))
    )
    (comp (ref "IC34")
      (value "XC6SLX150T-2FGG676C")
      (footprint "BGA676C100P26X26_2700X2700X260")
      (description "SPARTAN-6, FPGA, 676-Ball BGA, Commercial Grade, Pb-Free")
      (fields (field (name "MANUFACTURER") "XILINX") (field (name "AUTHOR") "CERN DEM JLC"))
      (libsource (lib "ICs And Semiconductors") (part "XC6SLX150T-2FGG676C"))
    )
  )
  (nets
    (net (code "1") (name "GND") (class "Default")
      (node (ref "C359") (pin "1") (pinfunction "1_1") (pintype "passive"))
      (node (ref "C360") (pin "1") (pinfunction "1_1") (pintype "passive"))
      (node (ref "C363") (pin "1") (pinfunction "1_1") (pintype "passive"))
      (node (ref "C366") (pin "1") (pinfunction "1_1") (pintype "passive"))
      (node (ref "C371") (pin "1") (pinfunction "1_1") (pintype "passive"))
      (node (ref "C372") (pin "1") (pinfunction "1_1") (pintype "passive"))
      (node (ref "C373") (pin "1") (pinfunction "1_1") (pintype "passive"))
      (node (ref "C377") (pin "1") (pinfunction "1_1") (pintype "passive"))
      (node (ref "C380") (pin "1") (pinfunction "1_1") (pintype "passive"))
      (node (ref "C381") (pin "1") (pinfunction "1_1") (pintype "passive"))
      (node (ref "C383") (pin "1") (pinfunction "1_1") (pintype "passive"))
      (node (ref "C385") (pin "1") (pinfunction "1_1") (pintype "passive"))
      (node (ref "C386") (pin "1") (pinfunction "1_1") (pintype "passive"))
      (node (ref "C388") (pin "1") (pinfunction "1_1") (pintype "passive"))
      (node (ref "C391") (pin "1") (pinfunction "1_1") (pintype "passive"))
      (node (ref "C393") (pin "1") (pinfunction "1_1") (pintype "passive"))
      (node (ref "C394") (pin "1") (pinfunction "1_1") (pintype "passive"))
      (node (ref "C395") (pin "1") (pinfunction "1_1") (pintype "passive"))
      (node (ref "C396") (pin "1") (pinfunction "1_1") (pintype "passive"))
      (node (ref "C397") (pin "1") (pinfunction "1_1") (pintype "passive"))
      (node (ref "C398") (pin "1") (pinfunction "1_1") (pintype "passive"))
      (node (ref "C399") (pin "1") (pinfunction "1_1") (pintype "passive"))
      (node (ref "C400") (pin "1") (pinfunction "1_1") (pintype "passive"))
      (node (ref "C401") (pin "1") (pinfunction "1_1") (pintype "passive"))
      (node (ref "C402") (pin "1") (pinfunction "1_1") (pintype "passive"))
      (node (ref "C403") (pin "1") (pinfunction "1_1") (pintype "passive"))
      (node (ref "C404") (pin "1") (pinfunction "1_1") (pintype "passive"))
      (node (ref "C407") (pin "1") (pinfunction "1_1") (pintype "passive"))
      (node (ref "C408") (pin "1") (pinfunction "1_1") (pintype "passive"))
      (node (ref "C409") (pin "1") (pinfunction "1_1") (pintype "passive"))
      (node (ref "C410") (pin "1") (pinfunction "1_1") (pintype "passive"))
      (node (ref "C411") (pin "1") (pinfunction "1_1") (pintype "passive"))
      (node (ref "C412") (pin "1") (pinfunction "1_1") (pintype "passive"))
      (node (ref "C413") (pin "1") (pinfunction "1_1") (pintype "passive"))
      (node (ref "C414") (pin "1") (pinfunction "1_1") (pintype "passive"))
      (node (ref "C415") (pin "1") (pinfunction "1_1") (pintype "passive"))
      (node (ref "C416") (pin "1") (pinfunction "1_1") (pintype "passive"))
      (node (ref "C417") (pin "1") (pinfunction "1_1") (pintype "passive"))
      (node (ref "C418") (pin "1") (pinfunction "1_1") (pintype "passive"))
      (node (ref "C419") (pin "1") (pinfunction "1_1") (pintype "passive"))
      (node (ref "C420") (pin "1") (pinfunction "1_1") (pintype "passive"))
      (node (ref "C421") (pin "1") (pinfunction "1_1") (pintype "passive"))
      (node (ref "C422") (pin "1") (pinfunction "1_1") (pintype "passive"))
      (node (ref "C423") (pin "1") (pinfunction "1_1") (pintype "passive"))
      (node (ref "C424") (pin "1") (pinfunction "1_1") (pintype "passive"))
      (node (ref "C425") (pin "1") (pinfunction "1_1") (pintype "passive"))
      (node (ref "C426") (pin "1") (pinfunction "1_1") (pintype "passive"))
      (node (ref "C427") (pin "1") (pinfunction "1_1") (pintype "passive"))
      (node (ref "C428") (pin "1") (pinfunction "1_1") (pintype "passive"))
      (node (ref "C429") (pin "1") (pinfunction "1_1") (pintype "passive"))
      (node (ref "C430") (pin "1") (pinfunction "1_1") (pintype "passive"))
      (node (ref "C431") (pin "1") (pinfunction "1_1") (pintype "passive"))
      (node (ref "C432") (pin "1") (pinfunction "1_1") (pintype "passive"))
      (node (ref "C433") (pin "1") (pinfunction "1_1") (pintype "passive"))
      (node (ref "C434") (pin "1") (pinfunction "1_1") (pintype "passive"))
      (node (ref "C435") (pin "1") (pinfunction "1_1") (pintype "passive"))
      (node (ref "C438") (pin "1") (pinfunction "1_1") (pintype "passive"))
      (node (ref "C439") (pin "1") (pinfunction "1_1") (pintype "passive"))
      (node (ref "C440") (pin "1") (pinfunction "1_1") (pintype "passive"))
      (node (ref "C441") (pin "1") (pinfunction "1_1") (pintype "passive"))
      (node (ref "C442") (pin "1") (pinfunction "1_1") (pintype "passive"))
      (node (ref "C443") (pin "1") (pinfunction "1_1") (pintype "passive"))
      (node (ref "C444") (pin "1") (pinfunction "1_1") (pintype "passive"))
      (node (ref "C445") (pin "1") (pinfunction "1_1") (pintype "passive"))
      (node (ref "C446") (pin "1") (pinfunction "1_1") (pintype "passive"))
      (node (ref "C448") (pin "1") (pinfunction "1_1") (pintype "passive"))
      (node (ref "C449") (pin "1") (pinfunction "1_1") (pintype "passive"))
      (node (ref "C450") (pin "1") (pinfunction "1_1") (pintype "passive"))
      (node (ref "C451") (pin "1") (pinfunction "1_1") (pintype "passive"))
      (node (ref "C452") (pin "1") (pinfunction "1_1") (pintype "passive"))
      (node (ref "C453") (pin "1") (pinfunction "1_1") (pintype "passive"))
      (node (ref "C454") (pin "1") (pinfunction "1_1") (pintype "passive"))
      (node (ref "C455") (pin "1") (pinfunction "1_1") (pintype "passive"))
      (node (ref "C456") (pin "1") (pinfunction "1_1") (pintype "passive"))
      (node (ref "C458") (pin "1") (pinfunction "1_1") (pintype "passive"))
      (node (ref "C459") (pin "1") (pinfunction "1_1") (pintype "passive"))
      (node (ref "C460") (pin "1") (pinfunction "1_1") (pintype "passive"))
      (node (ref "C462") (pin "1") (pinfunction "1_1") (pintype "passive"))
      (node (ref "C463") (pin "1") (pinfunction "1_1") (pintype "passive"))
      (node (ref "C466") (pin "1") (pinfunction "1_1") (pintype "passive"))
      (node (ref "C467") (pin "1") (pinfunction "1_1") (pintype "passive"))
      (node (ref "C469") (pin "1") (pinfunction "1_1") (pintype "passive"))
      (node (ref "C475") (pin "1") (pinfunction "1_1") (pintype "passive"))
      (node (ref "C478") (pin "1") (pinfunction "1_1") (pintype "passive"))
      (node (ref "C480") (pin "1") (pinfunction "1_1") (pintype "passive"))
      (node (ref "C481") (pin "1") (pinfunction "1_1") (pintype "passive"))
      (node (ref "C482") (pin "1") (pinfunction "1_1") (pintype "passive"))
      (node (ref "C483") (pin "1") (pinfunction "1_1") (pintype "passive"))
      (node (ref "C57") (pin "1") (pinfunction "1_1") (pintype "passive"))
      (node (ref "C58") (pin "1") (pinfunction "1_1") (pintype "passive"))
      (node (ref "C59") (pin "1") (pinfunction "1_1") (pintype "passive"))
      (node (ref "C60") (pin "1") (pinfunction "1_1") (pintype "passive"))
      (node (ref "C61") (pin "1") (pinfunction "1_1") (pintype "passive"))
      (node (ref "C62") (pin "1") (pinfunction "1_1") (pintype "passive"))
      (node (ref "C63") (pin "1") (pinfunction "1_1") (pintype "passive"))
      (node (ref "C65") (pin "1") (pinfunction "1_1") (pintype "passive"))
      (node (ref "C66") (pin "1") (pinfunction "1_1") (pintype "passive"))
      (node (ref "C67") (pin "1") (pinfunction "1_1") (pintype "passive"))
      (node (ref "C68") (pin "1") (pinfunction "1_1") (pintype "passive"))
      (node (ref "C69") (pin "1") (pinfunction "1_1") (pintype "passive"))
      (node (ref "IC34") (pin "A1") (pinfunction "GND_A1") (pintype "power_in"))
      (node (ref "IC34") (pin "A11") (pinfunction "GND_A11") (pintype "power_in"))
      (node (ref "IC34") (pin "A15") (pinfunction "GND_A15") (pintype "power_in"))
      (node (ref "IC34") (pin "A17") (pinfunction "GND_A17") (pintype "power_in"))
      (node (ref "IC34") (pin "A21") (pinfunction "GND_A21") (pintype "power_in"))
      (node (ref "IC34") (pin "A26") (pinfunction "GND_A26") (pintype "power_in"))
      (node (ref "IC34") (pin "A9") (pinfunction "GND_A9") (pintype "power_in"))
      (node (ref "IC34") (pin "AB16") (pinfunction "GND_AB16") (pintype "power_in"))
      (node (ref "IC34") (pin "AB2") (pinfunction "GND_AB2") (pintype "power_in"))
      (node (ref "IC34") (pin "AB20") (pinfunction "GND_AB20") (pintype "power_in"))
      (node (ref "IC34") (pin "AB25") (pinfunction "GND_AB25") (pintype "power_in"))
      (node (ref "IC34") (pin "AC11") (pinfunction "GND_AC11") (pintype "power_in"))
      (node (ref "IC34") (pin "AC13") (pinfunction "GND_AC13") (pintype "power_in"))
      (node (ref "IC34") (pin "AC15") (pinfunction "GND_AC15") (pintype "power_in"))
      (node (ref "IC34") (pin "AC17") (pinfunction "GND_AC17") (pintype "power_in"))
      (node (ref "IC34") (pin "AD19") (pinfunction "GND_AD19") (pintype "power_in"))
      (node (ref "IC34") (pin "AD21") (pinfunction "GND_AD21") (pintype "power_in"))
      (node (ref "IC34") (pin "AD7") (pinfunction "GND_AD7") (pintype "power_in"))
      (node (ref "IC34") (pin "AD9") (pinfunction "GND_AD9") (pintype "power_in"))
      (node (ref "IC34") (pin "AE10") (pinfunction "GND_AE10") (pintype "power_in"))
      (node (ref "IC34") (pin "AE18") (pinfunction "GND_AE18") (pintype "power_in"))
      (node (ref "IC34") (pin "AE20") (pinfunction "GND_AE20") (pintype "power_in"))
      (node (ref "IC34") (pin "AE22") (pinfunction "GND_AE22") (pintype "power_in"))
      (node (ref "IC34") (pin "AE6") (pinfunction "GND_AE6") (pintype "power_in"))
      (node (ref "IC34") (pin "AE8") (pinfunction "GND_AE8") (pintype "power_in"))
      (node (ref "IC34") (pin "AF1") (pinfunction "GND_AF1") (pintype "power_in"))
      (node (ref "IC34") (pin "AF10") (pinfunction "GND_AF10") (pintype "power_in"))
      (node (ref "IC34") (pin "AF12") (pinfunction "GND_AF12") (pintype "power_in"))
      (node (ref "IC34") (pin "AF16") (pinfunction "GND_AF16") (pintype "power_in"))
      (node (ref "IC34") (pin "AF18") (pinfunction "GND_AF18") (pintype "power_in"))
      (node (ref "IC34") (pin "AF26") (pinfunction "GND_AF26") (pintype "power_in"))
      (node (ref "IC34") (pin "B17") (pinfunction "GND_B17") (pintype "power_in"))
      (node (ref "IC34") (pin "B19") (pinfunction "GND_B19") (pintype "power_in"))
      (node (ref "IC34") (pin "B7") (pinfunction "GND_B7") (pintype "power_in"))
      (node (ref "IC34") (pin "B9") (pinfunction "GND_B9") (pintype "power_in"))
      (node (ref "IC34") (pin "C18") (pinfunction "GND_C18") (pintype "power_in"))
      (node (ref "IC34") (pin "C20") (pinfunction "GND_C20") (pintype "power_in"))
      (node (ref "IC34") (pin "C6") (pinfunction "GND_C6") (pintype "power_in"))
      (node (ref "IC34") (pin "C8") (pinfunction "GND_C8") (pintype "power_in"))
      (node (ref "IC34") (pin "D10") (pinfunction "GND_D10") (pintype "power_in"))
      (node (ref "IC34") (pin "D12") (pinfunction "GND_D12") (pintype "power_in"))
      (node (ref "IC34") (pin "D14") (pinfunction "GND_D14") (pintype "power_in"))
      (node (ref "IC34") (pin "D16") (pinfunction "GND_D16") (pintype "power_in"))
      (node (ref "IC34") (pin "D4") (pinfunction "GND_D4") (pintype "power_in"))
      (node (ref "IC34") (pin "E15") (pinfunction "GND_E15") (pintype "power_in"))
      (node (ref "IC34") (pin "E19") (pinfunction "GND_E19") (pintype "power_in"))
      (node (ref "IC34") (pin "E22") (pinfunction "GND_E22") (pintype "power_in"))
      (node (ref "IC34") (pin "E7") (pinfunction "GND_E7") (pintype "power_in"))
      (node (ref "IC34") (pin "F2") (pinfunction "GND_F2") (pintype "power_in"))
      (node (ref "IC34") (pin "F25") (pinfunction "GND_F25") (pintype "power_in"))
      (node (ref "IC34") (pin "G14") (pinfunction "GND_G14") (pintype "power_in"))
      (node (ref "IC34") (pin "H23") (pinfunction "GND_H23") (pintype "power_in"))
      (node (ref "IC34") (pin "H4") (pinfunction "GND_H4") (pintype "power_in"))
      (node (ref "IC34") (pin "J19") (pinfunction "GND_J19") (pintype "power_in"))
      (node (ref "IC34") (pin "J8") (pinfunction "GND_J8") (pintype "power_in"))
      (node (ref "IC34") (pin "K16") (pinfunction "GND_K16") (pintype "power_in"))
      (node (ref "IC34") (pin "K2") (pinfunction "GND_K2") (pintype "power_in"))
      (node (ref "IC34") (pin "K25") (pinfunction "GND_K25") (pintype "power_in"))
      (node (ref "IC34") (pin "L11") (pinfunction "GND_L11") (pintype "power_in"))
      (node (ref "IC34") (pin "L13") (pinfunction "GND_L13") (pintype "power_in"))
      (node (ref "IC34") (pin "L15") (pinfunction "GND_L15") (pintype "power_in"))
      (node (ref "IC34") (pin "L17") (pinfunction "GND_L17") (pintype "power_in"))
      (node (ref "IC34") (pin "M22") (pinfunction "GND_M22") (pintype "power_in"))
      (node (ref "IC34") (pin "M5") (pinfunction "GND_M5") (pintype "power_in"))
      (node (ref "IC34") (pin "N11") (pinfunction "GND_N11") (pintype "power_in"))
      (node (ref "IC34") (pin "N14") (pinfunction "GND_N14") (pintype "power_in"))
      (node (ref "IC34") (pin "P13") (pinfunction "GND_P13") (pintype "power_in"))
      (node (ref "IC34") (pin "P16") (pinfunction "GND_P16") (pintype "power_in"))
      (node (ref "IC34") (pin "P2") (pinfunction "GND_P2") (pintype "power_in"))
      (node (ref "IC34") (pin "P20") (pinfunction "GND_P20") (pintype "power_in"))
      (node (ref "IC34") (pin "P25") (pinfunction "GND_P25") (pintype "power_in"))
      (node (ref "IC34") (pin "P7") (pinfunction "GND_P7") (pintype "power_in"))
      (node (ref "IC34") (pin "T10") (pinfunction "GND_T10") (pintype "power_in"))
      (node (ref "IC34") (pin "T12") (pinfunction "GND_T12") (pintype "power_in"))
      (node (ref "IC34") (pin "T14") (pinfunction "GND_T14") (pintype "power_in"))
      (node (ref "IC34") (pin "T16") (pinfunction "GND_T16") (pintype "power_in"))
      (node (ref "IC34") (pin "T18") (pinfunction "GND_T18") (pintype "power_in"))
      (node (ref "IC34") (pin "T21") (pinfunction "GND_T21") (pintype "power_in"))
      (node (ref "IC34") (pin "T5") (pinfunction "GND_T5") (pintype "power_in"))
      (node (ref "IC34") (pin "U11") (pinfunction "GND_U11") (pintype "power_in"))
      (node (ref "IC34") (pin "U17") (pinfunction "GND_U17") (pintype "power_in"))
      (node (ref "IC34") (pin "V19") (pinfunction "RFUSE_V19") (pintype "input"))
      (node (ref "IC34") (pin "V2") (pinfunction "GND_V2") (pintype "power_in"))
      (node (ref "IC34") (pin "V22") (pinfunction "VBATT_V22") (pintype "input"))
      (node (ref "IC34") (pin "V25") (pinfunction "GND_V25") (pintype "power_in"))
      (node (ref "IC34") (pin "V8") (pinfunction "GND_V8") (pintype "power_in"))
      (node (ref "IC34") (pin "W22") (pinfunction "VFS_W22") (pintype "input"))
      (node (ref "IC34") (pin "Y10") (pinfunction "GND_Y10") (pintype "power_in"))
      (node (ref "IC34") (pin "Y14") (pinfunction "GND_Y14") (pintype "power_in"))
      (node (ref "IC34") (pin "Y23") (pinfunction "GND_Y23") (pintype "power_in"))
      (node (ref "IC34") (pin "Y4") (pinfunction "GND_Y4") (pintype "power_in"))
      (node (ref "IC34") (pin "Y7") (pinfunction "GND_Y7") (pintype "power_in"))
    )
    (net (code "2") (name "V1P2COREAPP") (class "Default")
      (node (ref "C393") (pin "2") (pinfunction "2_2") (pintype "passive"))
      (node (ref "C397") (pin "2") (pinfunction "2_2") (pintype "passive"))
      (node (ref "C399") (pin "2") (pinfunction "2_2") (pintype "passive"))
      (node (ref "C400") (pin "2") (pinfunction "2_2") (pintype "passive"))
      (node (ref "C409") (pin "2") (pinfunction "2_2") (pintype "passive"))
      (node (ref "C410") (pin "2") (pinfunction "2_2") (pintype "passive"))
      (node (ref "C411") (pin "2") (pinfunction "2_2") (pintype "passive"))
      (node (ref "C412") (pin "2") (pinfunction "2_2") (pintype "passive"))
      (node (ref "C413") (pin "2") (pinfunction "2_2") (pintype "passive"))
      (node (ref "C414") (pin "2") (pinfunction "2_2") (pintype "passive"))
      (node (ref "C415") (pin "2") (pinfunction "2_2") (pintype "passive"))
      (node (ref "C416") (pin "2") (pinfunction "2_2") (pintype "passive"))
      (node (ref "C417") (pin "2") (pinfunction "2_2") (pintype "passive"))
      (node (ref "C418") (pin "2") (pinfunction "2_2") (pintype "passive"))
      (node (ref "C423") (pin "2") (pinfunction "2_2") (pintype "passive"))
      (node (ref "C424") (pin "2") (pinfunction "2_2") (pintype "passive"))
      (node (ref "C425") (pin "2") (pinfunction "2_2") (pintype "passive"))
      (node (ref "C426") (pin "2") (pinfunction "2_2") (pintype "passive"))
      (node (ref "C427") (pin "2") (pinfunction "2_2") (pintype "passive"))
      (node (ref "C428") (pin "2") (pinfunction "2_2") (pintype "passive"))
      (node (ref "C429") (pin "2") (pinfunction "2_2") (pintype "passive"))
      (node (ref "C430") (pin "2") (pinfunction "2_2") (pintype "passive"))
      (node (ref "C431") (pin "2") (pinfunction "2_2") (pintype "passive"))
      (node (ref "C432") (pin "2") (pinfunction "2_2") (pintype "passive"))
      (node (ref "C441") (pin "2") (pinfunction "2_2") (pintype "passive"))
      (node (ref "C442") (pin "2") (pinfunction "2_2") (pintype "passive"))
      (node (ref "C443") (pin "2") (pinfunction "2_2") (pintype "passive"))
      (node (ref "C446") (pin "2") (pinfunction "2_2") (pintype "passive"))
      (node (ref "C482") (pin "2") (pinfunction "2_2") (pintype "passive"))
      (node (ref "C483") (pin "2") (pinfunction "2_2") (pintype "passive"))
      (node (ref "C61") (pin "2") (pinfunction "2_2") (pintype "passive"))
      (node (ref "C62") (pin "2") (pinfunction "2_2") (pintype "passive"))
      (node (ref "C66") (pin "2") (pinfunction "2_2") (pintype "passive"))
      (node (ref "C68") (pin "2") (pinfunction "2_2") (pintype "passive"))
      (node (ref "C69") (pin "2") (pinfunction "2_2") (pintype "passive"))
      (node (ref "IC34") (pin "K11") (pinfunction "VCCINT_K11") (pintype "power_in"))
      (node (ref "IC34") (pin "K17") (pinfunction "VCCINT_K17") (pintype "power_in"))
      (node (ref "IC34") (pin "L12") (pinfunction "VCCINT_L12") (pintype "power_in"))
      (node (ref "IC34") (pin "L14") (pinfunction "VCCINT_L14") (pintype "power_in"))
      (node (ref "IC34") (pin "L16") (pinfunction "VCCINT_L16") (pintype "power_in"))
      (node (ref "IC34") (pin "M11") (pinfunction "VCCINT_M11") (pintype "power_in"))
      (node (ref "IC34") (pin "M12") (pinfunction "VCCINT_M12") (pintype "power_in"))
      (node (ref "IC34") (pin "M13") (pinfunction "VCCINT_M13") (pintype "power_in"))
      (node (ref "IC34") (pin "M14") (pinfunction "VCCINT_M14") (pintype "power_in"))
      (node (ref "IC34") (pin "M15") (pinfunction "VCCINT_M15") (pintype "power_in"))
      (node (ref "IC34") (pin "M16") (pinfunction "VCCINT_M16") (pintype "power_in"))
      (node (ref "IC34") (pin "N12") (pinfunction "VCCINT_N12") (pintype "power_in"))
      (node (ref "IC34") (pin "N13") (pinfunction "VCCINT_N13") (pintype "power_in"))
      (node (ref "IC34") (pin "N15") (pinfunction "VCCINT_N15") (pintype "power_in"))
      (node (ref "IC34") (pin "N16") (pinfunction "VCCINT_N16") (pintype "power_in"))
      (node (ref "IC34") (pin "P11") (pinfunction "VCCINT_P11") (pintype "power_in"))
      (node (ref "IC34") (pin "P12") (pinfunction "VCCINT_P12") (pintype "power_in"))
      (node (ref "IC34") (pin "P14") (pinfunction "VCCINT_P14") (pintype "power_in"))
      (node (ref "IC34") (pin "P15") (pinfunction "VCCINT_P15") (pintype "power_in"))
      (node (ref "IC34") (pin "R11") (pinfunction "VCCINT_R11") (pintype "power_in"))
      (node (ref "IC34") (pin "R12") (pinfunction "VCCINT_R12") (pintype "power_in"))
      (node (ref "IC34") (pin "R13") (pinfunction "VCCINT_R13") (pintype "power_in"))
      (node (ref "IC34") (pin "R14") (pinfunction "VCCINT_R14") (pintype "power_in"))
      (node (ref "IC34") (pin "R15") (pinfunction "VCCINT_R15") (pintype "power_in"))
      (node (ref "IC34") (pin "R16") (pinfunction "VCCINT_R16") (pintype "power_in"))
      (node (ref "IC34") (pin "R17") (pinfunction "VCCINT_R17") (pintype "power_in"))
      (node (ref "IC34") (pin "T11") (pinfunction "VCCINT_T11") (pintype "power_in"))
      (node (ref "IC34") (pin "T13") (pinfunction "VCCINT_T13") (pintype "power_in"))
      (node (ref "IC34") (pin "T15") (pinfunction "VCCINT_T15") (pintype "power_in"))
      (node (ref "IC34") (pin "T17") (pinfunction "VCCINT_T17") (pintype "power_in"))
      (node (ref "IC34") (pin "U10") (pinfunction "VCCINT_U10") (pintype "power_in"))
      (node (ref "IC34") (pin "U16") (pinfunction "VCCINT_U16") (pintype "power_in"))
    )
    (net (code "3") (name "V3P3APP") (class "Default")
      (node (ref "C363") (pin "2") (pinfunction "2_2") (pintype "passive"))
      (node (ref "C371") (pin "2") (pinfunction "2_2") (pintype "passive"))
      (node (ref "C372") (pin "2") (pinfunction "2_2") (pintype "passive"))
      (node (ref "C377") (pin "2") (pinfunction "2_2") (pintype "passive"))
      (node (ref "C381") (pin "2") (pinfunction "2_2") (pintype "passive"))
      (node (ref "C385") (pin "2") (pinfunction "2_2") (pintype "passive"))
      (node (ref "C386") (pin "2") (pinfunction "2_2") (pintype "passive"))
      (node (ref "C391") (pin "2") (pinfunction "2_2") (pintype "passive"))
      (node (ref "C394") (pin "2") (pinfunction "2_2") (pintype "passive"))
      (node (ref "C395") (pin "2") (pinfunction "2_2") (pintype "passive"))
      (node (ref "C396") (pin "2") (pinfunction "2_2") (pintype "passive"))
      (node (ref "C398") (pin "2") (pinfunction "2_2") (pintype "passive"))
      (node (ref "C402") (pin "2") (pinfunction "2_2") (pintype "passive"))
      (node (ref "C403") (pin "2") (pinfunction "2_2") (pintype "passive"))
      (node (ref "C404") (pin "2") (pinfunction "2_2") (pintype "passive"))
      (node (ref "C407") (pin "2") (pinfunction "2_2") (pintype "passive"))
      (node (ref "C408") (pin "2") (pinfunction "2_2") (pintype "passive"))
      (node (ref "C419") (pin "2") (pinfunction "2_2") (pintype "passive"))
      (node (ref "C420") (pin "2") (pinfunction "2_2") (pintype "passive"))
      (node (ref "C421") (pin "2") (pinfunction "2_2") (pintype "passive"))
      (node (ref "C422") (pin "2") (pinfunction "2_2") (pintype "passive"))
      (node (ref "C433") (pin "2") (pinfunction "2_2") (pintype "passive"))
      (node (ref "C434") (pin "2") (pinfunction "2_2") (pintype "passive"))
      (node (ref "C435") (pin "2") (pinfunction "2_2") (pintype "passive"))
      (node (ref "C438") (pin "2") (pinfunction "2_2") (pintype "passive"))
      (node (ref "C439") (pin "2") (pinfunction "2_2") (pintype "passive"))
      (node (ref "C440") (pin "2") (pinfunction "2_2") (pintype "passive"))
      (node (ref "C444") (pin "2") (pinfunction "2_2") (pintype "passive"))
      (node (ref "C445") (pin "2") (pinfunction "2_2") (pintype "passive"))
      (node (ref "C448") (pin "2") (pinfunction "2_2") (pintype "passive"))
      (node (ref "C449") (pin "2") (pinfunction "2_2") (pintype "passive"))
      (node (ref "C451") (pin "2") (pinfunction "2_2") (pintype "passive"))
      (node (ref "C454") (pin "2") (pinfunction "2_2") (pintype "passive"))
      (node (ref "C455") (pin "2") (pinfunction "2_2") (pintype "passive"))
      (node (ref "C456") (pin "2") (pinfunction "2_2") (pintype "passive"))
      (node (ref "C458") (pin "2") (pinfunction "2_2") (pintype "passive"))
      (node (ref "C460") (pin "2") (pinfunction "2_2") (pintype "passive"))
      (node (ref "C463") (pin "2") (pinfunction "2_2") (pintype "passive"))
      (node (ref "C466") (pin "2") (pinfunction "2_2") (pintype "passive"))
      (node (ref "C467") (pin "2") (pinfunction "2_2") (pintype "passive"))
      (node (ref "C478") (pin "2") (pinfunction "2_2") (pintype "passive"))
      (node (ref "C480") (pin "2") (pinfunction "2_2") (pintype "passive"))
      (node (ref "C57") (pin "2") (pinfunction "2_2") (pintype "passive"))
      (node (ref "C58") (pin "2") (pinfunction "2_2") (pintype "passive"))
      (node (ref "C59") (pin "2") (pinfunction "2_2") (pintype "passive"))
      (node (ref "C63") (pin "2") (pinfunction "2_2") (pintype "passive"))
      (node (ref "C67") (pin "2") (pinfunction "2_2") (pintype "passive"))
      (node (ref "IC34") (pin "AA5") (pinfunction "VCCAUX_AA5") (pintype "power_in"))
      (node (ref "IC34") (pin "AB18") (pinfunction "VCCAUX_AB18") (pintype "power_in"))
      (node (ref "IC34") (pin "AB23") (pinfunction "VCCO_1_AB23") (pintype "power_in"))
      (node (ref "IC34") (pin "AB8") (pinfunction "VCCAUX_AB8") (pintype "power_in"))
      (node (ref "IC34") (pin "AC21") (pinfunction "VCCAUX_AC21") (pintype "power_in"))
      (node (ref "IC34") (pin "AC7") (pinfunction "VCCAUX_AC7") (pintype "power_in"))
      (node (ref "IC34") (pin "AD2") (pinfunction "VCCO_3_AD2") (pintype "power_in"))
      (node (ref "IC34") (pin "AD25") (pinfunction "VCCO_1_AD25") (pintype "power_in"))
      (node (ref "IC34") (pin "D2") (pinfunction "VCCO_4_D2") (pintype "power_in"))
      (node (ref "IC34") (pin "D20") (pinfunction "VCCAUX_D20") (pintype "power_in"))
      (node (ref "IC34") (pin "D25") (pinfunction "VCCO_5_D25") (pintype "power_in"))
      (node (ref "IC34") (pin "D6") (pinfunction "VCCAUX_D6") (pintype "power_in"))
      (node (ref "IC34") (pin "E17") (pinfunction "VCCAUX_E17") (pintype "power_in"))
      (node (ref "IC34") (pin "F4") (pinfunction "VCCO_4_F4") (pintype "power_in"))
      (node (ref "IC34") (pin "G22") (pinfunction "VCCO_5_G22") (pintype "power_in"))
      (node (ref "IC34") (pin "G5") (pinfunction "VCCAUX_G5") (pintype "power_in"))
      (node (ref "IC34") (pin "H2") (pinfunction "VCCO_4_H2") (pintype "power_in"))
      (node (ref "IC34") (pin "H25") (pinfunction "VCCO_5_H25") (pintype "power_in"))
      (node (ref "IC34") (pin "J10") (pinfunction "VCCAUX_J10") (pintype "power_in"))
      (node (ref "IC34") (pin "J18") (pinfunction "VCCAUX_J18") (pintype "power_in"))
      (node (ref "IC34") (pin "J21") (pinfunction "VCCO_5_J21") (pintype "power_in"))
      (node (ref "IC34") (pin "J6") (pinfunction "VCCO_4_J6") (pintype "power_in"))
      (node (ref "IC34") (pin "K13") (pinfunction "VCCAUX_K13") (pintype "power_in"))
      (node (ref "IC34") (pin "K15") (pinfunction "VCCAUX_K15") (pintype "power_in"))
      (node (ref "IC34") (pin "K23") (pinfunction "VCCO_5_K23") (pintype "power_in"))
      (node (ref "IC34") (pin "K4") (pinfunction "VCCO_4_K4") (pintype "power_in"))
      (node (ref "IC34") (pin "L18") (pinfunction "VCCAUX_L18") (pintype "power_in"))
      (node (ref "IC34") (pin "L22") (pinfunction "VCCAUX_L22") (pintype "power_in"))
      (node (ref "IC34") (pin "L5") (pinfunction "VCCAUX_L5") (pintype "power_in"))
      (node (ref "IC34") (pin "M17") (pinfunction "VCCAUX_M17") (pintype "power_in"))
      (node (ref "IC34") (pin "M2") (pinfunction "VCCO_4_M2") (pintype "power_in"))
      (node (ref "IC34") (pin "M20") (pinfunction "VCCO_5_M20") (pintype "power_in"))
      (node (ref "IC34") (pin "M25") (pinfunction "VCCO_5_M25") (pintype "power_in"))
      (node (ref "IC34") (pin "M7") (pinfunction "VCCO_4_M7") (pintype "power_in"))
      (node (ref "IC34") (pin "N10") (pinfunction "VCCAUX_N10") (pintype "power_in"))
      (node (ref "IC34") (pin "P18") (pinfunction "VCCO_1_P18") (pintype "power_in"))
      (node (ref "IC34") (pin "P23") (pinfunction "VCCO_1_P23") (pintype "power_in"))
      (node (ref "IC34") (pin "P4") (pinfunction "VCCO_3_P4") (pintype "power_in"))
      (node (ref "IC34") (pin "P9") (pinfunction "VCCO_3_P9") (pintype "power_in"))
      (node (ref "IC34") (pin "R22") (pinfunction "VCCAUX_R22") (pintype "power_in"))
      (node (ref "IC34") (pin "T2") (pinfunction "VCCO_3_T2") (pintype "power_in"))
      (node (ref "IC34") (pin "T25") (pinfunction "VCCO_1_T25") (pintype "power_in"))
      (node (ref "IC34") (pin "T7") (pinfunction "VCCO_3_T7") (pintype "power_in"))
      (node (ref "IC34") (pin "U12") (pinfunction "VCCAUX_U12") (pintype "power_in"))
      (node (ref "IC34") (pin "U14") (pinfunction "VCCAUX_U14") (pintype "power_in"))
      (node (ref "IC34") (pin "U18") (pinfunction "VCCAUX_U18") (pintype "power_in"))
      (node (ref "IC34") (pin "U6") (pinfunction "VCCAUX_U6") (pintype "power_in"))
      (node (ref "IC34") (pin "V17") (pinfunction "VCCAUX_V17") (pintype "power_in"))
      (node (ref "IC34") (pin "V9") (pinfunction "VCCAUX_V9") (pintype "power_in"))
      (node (ref "IC34") (pin "W13") (pinfunction "VCCAUX_W13") (pintype "power_in"))
      (node (ref "IC34") (pin "W21") (pinfunction "VCCO_1_W21") (pintype "power_in"))
      (node (ref "IC34") (pin "W23") (pinfunction "VCCO_1_W23") (pintype "power_in"))
      (node (ref "IC34") (pin "W4") (pinfunction "VCCO_3_W4") (pintype "power_in"))
      (node (ref "IC34") (pin "W6") (pinfunction "VCCO_3_W6") (pintype "power_in"))
      (node (ref "IC34") (pin "Y2") (pinfunction "VCCO_3_Y2") (pintype "power_in"))
      (node (ref "IC34") (pin "Y25") (pinfunction "VCCO_1_Y25") (pintype "power_in"))
    )
    (net (code "4") (name "VADJ1") (class "Default")
      (node (ref "C359") (pin "2") (pinfunction "2_2") (pintype "passive"))
      (node (ref "C360") (pin "2") (pinfunction "2_2") (pintype "passive"))
      (node (ref "C366") (pin "2") (pinfunction "2_2") (pintype "passive"))
      (node (ref "C373") (pin "2") (pinfunction "2_2") (pintype "passive"))
      (node (ref "C380") (pin "2") (pinfunction "2_2") (pintype "passive"))
      (node (ref "C383") (pin "2") (pinfunction "2_2") (pintype "passive"))
      (node (ref "C388") (pin "2") (pinfunction "2_2") (pintype "passive"))
      (node (ref "C401") (pin "2") (pinfunction "2_2") (pintype "passive"))
      (node (ref "C60") (pin "2") (pinfunction "2_2") (pintype "passive"))
      (node (ref "IC34") (pin "B13") (pinfunction "VCCO_0_B13") (pintype "power_in"))
      (node (ref "IC34") (pin "C22") (pinfunction "VCCO_0_C22") (pintype "power_in"))
      (node (ref "IC34") (pin "C4") (pinfunction "VCCO_0_C4") (pintype "power_in"))
      (node (ref "IC34") (pin "E21") (pinfunction "VCCO_0_E21") (pintype "power_in"))
      (node (ref "IC34") (pin "F13") (pinfunction "VCCO_0_F13") (pintype "power_in"))
      (node (ref "IC34") (pin "F8") (pinfunction "VCCO_0_F8") (pintype "power_in"))
      (node (ref "IC34") (pin "G18") (pinfunction "VCCO_0_G18") (pintype "power_in"))
      (node (ref "IC34") (pin "H11") (pinfunction "VCCO_0_H11") (pintype "power_in"))
      (node (ref "IC34") (pin "H16") (pinfunction "VCCO_0_H16") (pintype "power_in"))
      (node (ref "IC34") (pin "J14") (pinfunction "VCCO_0_J14") (pintype "power_in"))
    )
    (net (code "5") (name "VADJ2") (class "Default")
      (node (ref "C450") (pin "2") (pinfunction "2_2") (pintype "passive"))
      (node (ref "C452") (pin "2") (pinfunction "2_2") (pintype "passive"))
      (node (ref "C453") (pin "2") (pinfunction "2_2") (pintype "passive"))
      (node (ref "C459") (pin "2") (pinfunction "2_2") (pintype "passive"))
      (node (ref "C462") (pin "2") (pinfunction "2_2") (pintype "passive"))
      (node (ref "C469") (pin "2") (pinfunction "2_2") (pintype "passive"))
      (node (ref "C475") (pin "2") (pinfunction "2_2") (pintype "passive"))
      (node (ref "C481") (pin "2") (pinfunction "2_2") (pintype "passive"))
      (node (ref "C65") (pin "2") (pinfunction "2_2") (pintype "passive"))
      (node (ref "IC34") (pin "AA14") (pinfunction "VCCO_2_AA14") (pintype "power_in"))
      (node (ref "IC34") (pin "AA20") (pinfunction "VCCO_2_AA20") (pintype "power_in"))
      (node (ref "IC34") (pin "AB6") (pinfunction "VCCO_2_AB6") (pintype "power_in"))
      (node (ref "IC34") (pin "AE14") (pinfunction "VCCO_2_AE14") (pintype "power_in"))
      (node (ref "IC34") (pin "AE23") (pinfunction "VCCO_2_AE23") (pintype "power_in"))
      (node (ref "IC34") (pin "AE4") (pinfunction "VCCO_2_AE4") (pintype "power_in"))
      (node (ref "IC34") (pin "W11") (pinfunction "VCCO_2_W11") (pintype "power_in"))
      (node (ref "IC34") (pin "W15") (pinfunction "VCCO_2_W15") (pintype "power_in"))
      (node (ref "IC34") (pin "Y18") (pinfunction "VCCO_2_Y18") (pintype "power_in"))
      (node (ref "IC34") (pin "Y8") (pinfunction "VCCO_2_Y8") (pintype "power_in"))
    )
  )
)
